# 5-Connector.net
KiCad netlist of a schematic drawn in Altium Designer
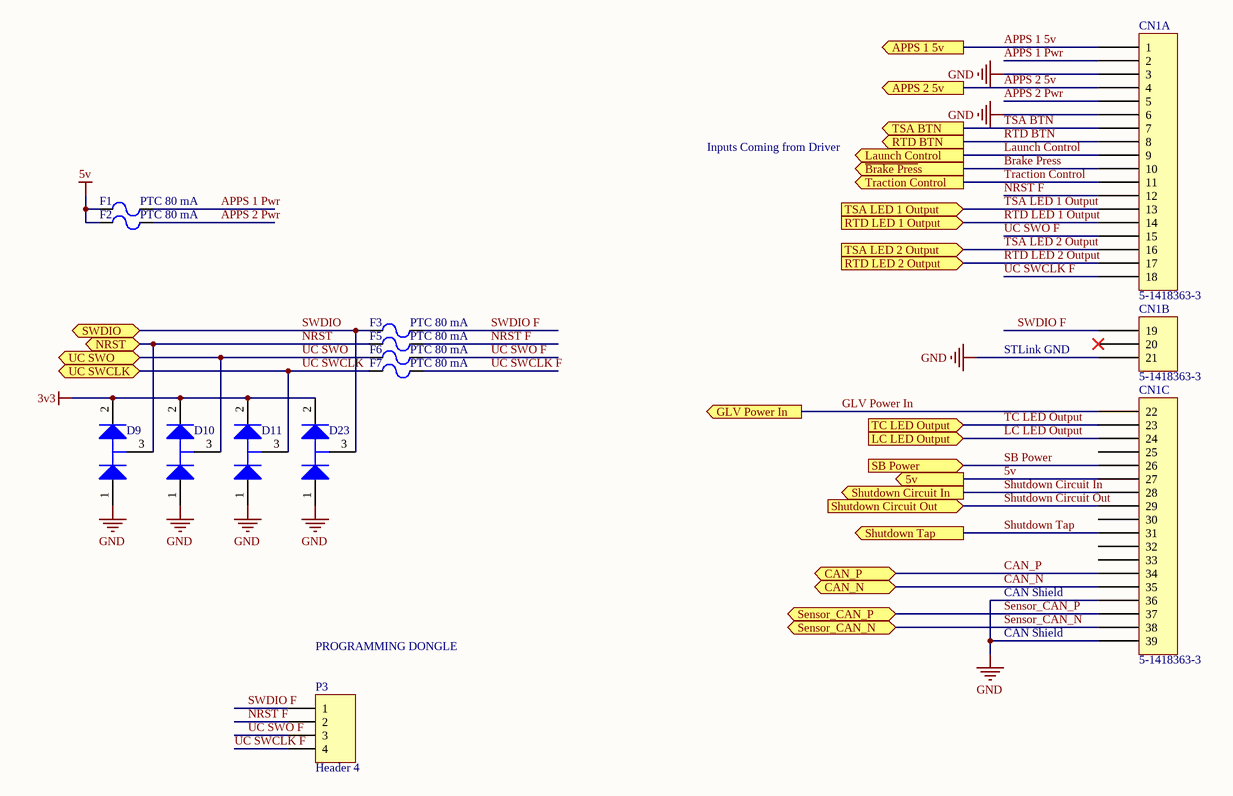
[diagram p0: 5-Connector.SchDoc]

(export (version "E")
  (design (tool "Eeschema 10.0.6"))
  (components
    (comp (ref "CN1")
      (value "5-1418363-3")
      (footprint "5-1418363-3")
      (description "Levyseal 90 degree 39 pin header")
      (libsource (lib "VCB20") (part "5-1418363-3"))
    )
    (comp (ref "D9")
      (value "SZNUP1301ML3T1G")
      (footprint "ONSC-SOT-23-3-318-08_V")
      (fields (field (name "MANUFACTURER") "On Semiconductor"))
      (libsource (lib "Altium Content Vault") (part "ONSC-NUP1301-SOT-23-3-318-08"))
    )
    (comp (ref "D10")
      (value "SZNUP1301ML3T1G")
      (footprint "ONSC-SOT-23-3-318-08_V")
      (fields (field (name "MANUFACTURER") "On Semiconductor"))
      (libsource (lib "Altium Content Vault") (part "ONSC-NUP1301-SOT-23-3-318-08"))
    )
    (comp (ref "D11")
      (value "SZNUP1301ML3T1G")
      (footprint "ONSC-SOT-23-3-318-08_V")
      (fields (field (name "MANUFACTURER") "On Semiconductor"))
      (libsource (lib "Altium Content Vault") (part "ONSC-NUP1301-SOT-23-3-318-08"))
    )
    (comp (ref "D23")
      (value "SZNUP1301ML3T1G")
      (footprint "ONSC-SOT-23-3-318-08_V")
      (fields (field (name "MANUFACTURER") "On Semiconductor"))
      (libsource (lib "Altium Content Vault") (part "ONSC-NUP1301-SOT-23-3-318-08"))
    )
    (comp (ref "F1")
      (value "PTC 80 mA")
      (footprint "0603 fuse")
      (description "0ZCM0008FF2G")
      (libsource (lib "VCU Library") (part "PTC fuse 80mA 0ZCM0008FF2G"))
    )
    (comp (ref "F2")
      (value "PTC 80 mA")
      (footprint "0603 fuse")
      (description "0ZCM0008FF2G")
      (libsource (lib "VCU Library") (part "PTC fuse 80mA 0ZCM0008FF2G"))
    )
    (comp (ref "F3")
      (value "PTC 80 mA")
      (footprint "0603 fuse")
      (description "0ZCM0008FF2G")
      (libsource (lib "VCU Library") (part "PTC fuse 80mA 0ZCM0008FF2G"))
    )
    (comp (ref "F5")
      (value "PTC 80 mA")
      (footprint "0603 fuse")
      (description "0ZCM0008FF2G")
      (libsource (lib "VCU Library") (part "PTC fuse 80mA 0ZCM0008FF2G"))
    )
    (comp (ref "F6")
      (value "PTC 80 mA")
      (footprint "0603 fuse")
      (description "0ZCM0008FF2G")
      (libsource (lib "VCU Library") (part "PTC fuse 80mA 0ZCM0008FF2G"))
    )
    (comp (ref "F7")
      (value "PTC 80 mA")
      (footprint "0603 fuse")
      (description "0ZCM0008FF2G")
      (libsource (lib "VCU Library") (part "PTC fuse 80mA 0ZCM0008FF2G"))
    )
    (comp (ref "P3")
      (value "Header 4")
      (footprint "HDR1X4")
      (description "Header, 4-Pin")
      (fields (field (name "PUBLISHER") "Altium Limited"))
      (libsource (lib "Miscellaneous Connectors") (part "Header 4"))
    )
  )
  (nets
    (net (code "1") (name "/APPS 1 5v") (class "Default")
      (node (ref "CN1") (pin "1") (pinfunction "1_1") (pintype "passive"))
    )
    (net (code "2") (name "/APPS 1 Pwr") (class "Default")
      (node (ref "CN1") (pin "2") (pinfunction "2_2") (pintype "passive"))
      (node (ref "F1") (pin "2") (pinfunction "2_2") (pintype "passive"))
    )
    (net (code "3") (name "/APPS 2 5v") (class "Default")
      (node (ref "CN1") (pin "4") (pinfunction "4_4") (pintype "passive"))
    )
    (net (code "4") (name "/APPS 2 Pwr") (class "Default")
      (node (ref "CN1") (pin "5") (pinfunction "5_5") (pintype "passive"))
      (node (ref "F2") (pin "2") (pinfunction "2_2") (pintype "passive"))
    )
    (net (code "5") (name "/CAN_N") (class "Default")
      (node (ref "CN1") (pin "35") (pinfunction "35_35") (pintype "passive"))
    )
    (net (code "6") (name "/CAN_P") (class "Default")
      (node (ref "CN1") (pin "34") (pinfunction "34_34") (pintype "passive"))
    )
    (net (code "7") (name "/GLV Power In") (class "Default")
      (node (ref "CN1") (pin "22") (pinfunction "22_22") (pintype "passive"))
    )
    (net (code "8") (name "/LC LED Output") (class "Default")
      (node (ref "CN1") (pin "24") (pinfunction "24_24") (pintype "passive"))
    )
    (net (code "9") (name "/Launch Control") (class "Default")
      (node (ref "CN1") (pin "9") (pinfunction "9_9") (pintype "passive"))
    )
    (net (code "10") (name "/NRST") (class "Default")
      (node (ref "D9") (pin "3") (pinfunction "K/A_3") (pintype "passive"))
      (node (ref "F5") (pin "1") (pinfunction "1_1") (pintype "passive"))
    )
    (net (code "11") (name "/NRST F") (class "Default")
      (node (ref "CN1") (pin "12") (pinfunction "12_12") (pintype "passive"))
      (node (ref "F5") (pin "2") (pinfunction "2_2") (pintype "passive"))
      (node (ref "P3") (pin "2") (pinfunction "2_2") (pintype "passive"))
    )
    (net (code "12") (name "/RTD BTN") (class "Default")
      (node (ref "CN1") (pin "8") (pinfunction "8_8") (pintype "passive"))
    )
    (net (code "13") (name "/RTD LED 1 Output") (class "Default")
      (node (ref "CN1") (pin "14") (pinfunction "14_14") (pintype "passive"))
    )
    (net (code "14") (name "/RTD LED 2 Output") (class "Default")
      (node (ref "CN1") (pin "17") (pinfunction "17_17") (pintype "passive"))
    )
    (net (code "15") (name "/SB Power") (class "Default")
      (node (ref "CN1") (pin "26") (pinfunction "26_26") (pintype "passive"))
    )
    (net (code "16") (name "/SWDIO") (class "Default")
      (node (ref "D23") (pin "3") (pinfunction "K/A_3") (pintype "passive"))
      (node (ref "F3") (pin "1") (pinfunction "1_1") (pintype "passive"))
    )
    (net (code "17") (name "/SWDIO F") (class "Default")
      (node (ref "CN1") (pin "19") (pinfunction "19_19") (pintype "passive"))
      (node (ref "F3") (pin "2") (pinfunction "2_2") (pintype "passive"))
      (node (ref "P3") (pin "1") (pinfunction "1_1") (pintype "passive"))
    )
    (net (code "18") (name "/Sensor_CAN_N") (class "Default")
      (node (ref "CN1") (pin "38") (pinfunction "38_38") (pintype "passive"))
    )
    (net (code "19") (name "/Sensor_CAN_P") (class "Default")
      (node (ref "CN1") (pin "37") (pinfunction "37_37") (pintype "passive"))
    )
    (net (code "20") (name "/Shutdown Circuit In") (class "Default")
      (node (ref "CN1") (pin "28") (pinfunction "28_28") (pintype "passive"))
    )
    (net (code "21") (name "/Shutdown Circuit Out") (class "Default")
      (node (ref "CN1") (pin "29") (pinfunction "29_29") (pintype "passive"))
    )
    (net (code "22") (name "/Shutdown Tap") (class "Default")
      (node (ref "CN1") (pin "31") (pinfunction "31_31") (pintype "passive"))
    )
    (net (code "23") (name "/TC LED Output") (class "Default")
      (node (ref "CN1") (pin "23") (pinfunction "23_23") (pintype "passive"))
    )
    (net (code "24") (name "/TSA BTN") (class "Default")
      (node (ref "CN1") (pin "7") (pinfunction "7_7") (pintype "passive"))
    )
    (net (code "25") (name "/TSA LED 1 Output") (class "Default")
      (node (ref "CN1") (pin "13") (pinfunction "13_13") (pintype "passive"))
    )
    (net (code "26") (name "/TSA LED 2 Output") (class "Default")
      (node (ref "CN1") (pin "16") (pinfunction "16_16") (pintype "passive"))
    )
    (net (code "27") (name "/Traction Control") (class "Default")
      (node (ref "CN1") (pin "11") (pinfunction "11_11") (pintype "passive"))
    )
    (net (code "28") (name "/UC SWCLK") (class "Default")
      (node (ref "D11") (pin "3") (pinfunction "K/A_3") (pintype "passive"))
      (node (ref "F7") (pin "1") (pinfunction "1_1") (pintype "passive"))
    )
    (net (code "29") (name "/UC SWCLK F") (class "Default")
      (node (ref "CN1") (pin "18") (pinfunction "18_18") (pintype "passive"))
      (node (ref "F7") (pin "2") (pinfunction "2_2") (pintype "passive"))
      (node (ref "P3") (pin "4") (pinfunction "4_4") (pintype "passive"))
    )
    (net (code "30") (name "/UC SWO") (class "Default")
      (node (ref "D10") (pin "3") (pinfunction "K/A_3") (pintype "passive"))
      (node (ref "F6") (pin "1") (pinfunction "1_1") (pintype "passive"))
    )
    (net (code "31") (name "/UC SWO F") (class "Default")
      (node (ref "CN1") (pin "15") (pinfunction "15_15") (pintype "passive"))
      (node (ref "F6") (pin "2") (pinfunction "2_2") (pintype "passive"))
      (node (ref "P3") (pin "3") (pinfunction "3_3") (pintype "passive"))
    )
    (net (code "32") (name "/~{Brake Pres}s") (class "Default")
      (node (ref "CN1") (pin "10") (pinfunction "10_10") (pintype "passive"))
    )
    (net (code "33") (name "3v3") (class "Default")
      (node (ref "D10") (pin "2") (pinfunction "K_2") (pintype "passive"))
      (node (ref "D11") (pin "2") (pinfunction "K_2") (pintype "passive"))
      (node (ref "D23") (pin "2") (pinfunction "K_2") (pintype "passive"))
      (node (ref "D9") (pin "2") (pinfunction "K_2") (pintype "passive"))
    )
    (net (code "34") (name "5v") (class "Default")
      (node (ref "CN1") (pin "27") (pinfunction "27_27") (pintype "passive"))
      (node (ref "F1") (pin "1") (pinfunction "1_1") (pintype "passive"))
      (node (ref "F2") (pin "1") (pinfunction "1_1") (pintype "passive"))
    )
    (net (code "35") (name "GND") (class "Default")
      (node (ref "CN1") (pin "21") (pinfunction "21_21") (pintype "passive"))
      (node (ref "CN1") (pin "3") (pinfunction "3_3") (pintype "passive"))
      (node (ref "CN1") (pin "36") (pinfunction "36_36") (pintype "passive"))
      (node (ref "CN1") (pin "39") (pinfunction "39_39") (pintype "passive"))
      (node (ref "CN1") (pin "6") (pinfunction "6_6") (pintype "passive"))
      (node (ref "D10") (pin "1") (pinfunction "A_1") (pintype "passive"))
      (node (ref "D11") (pin "1") (pinfunction "A_1") (pintype "passive"))
      (node (ref "D23") (pin "1") (pinfunction "A_1") (pintype "passive"))
      (node (ref "D9") (pin "1") (pinfunction "A_1") (pintype "passive"))
    )
    (net (code "36") (name "unconnected-(CN1-Pad20)") (class "Default")
      (node (ref "CN1") (pin "20") (pinfunction "20_20") (pintype "passive+no_connect"))
    )
    (net (code "37") (name "unconnected-(CN1-Pad25)") (class "Default")
      (node (ref "CN1") (pin "25") (pinfunction "25_25") (pintype "passive"))
    )
    (net (code "38") (name "unconnected-(CN1-Pad30)") (class "Default")
      (node (ref "CN1") (pin "30") (pinfunction "30_30") (pintype "passive"))
    )
    (net (code "39") (name "unconnected-(CN1-Pad32)") (class "Default")
      (node (ref "CN1") (pin "32") (pinfunction "32_32") (pintype "passive"))
    )
    (net (code "40") (name "unconnected-(CN1-Pad33)") (class "Default")
      (node (ref "CN1") (pin "33") (pinfunction "33_33") (pintype "passive"))
    )
  )
)
